# SimpleServo2.net
KiCad netlist of a schematic drawn in EAGLE
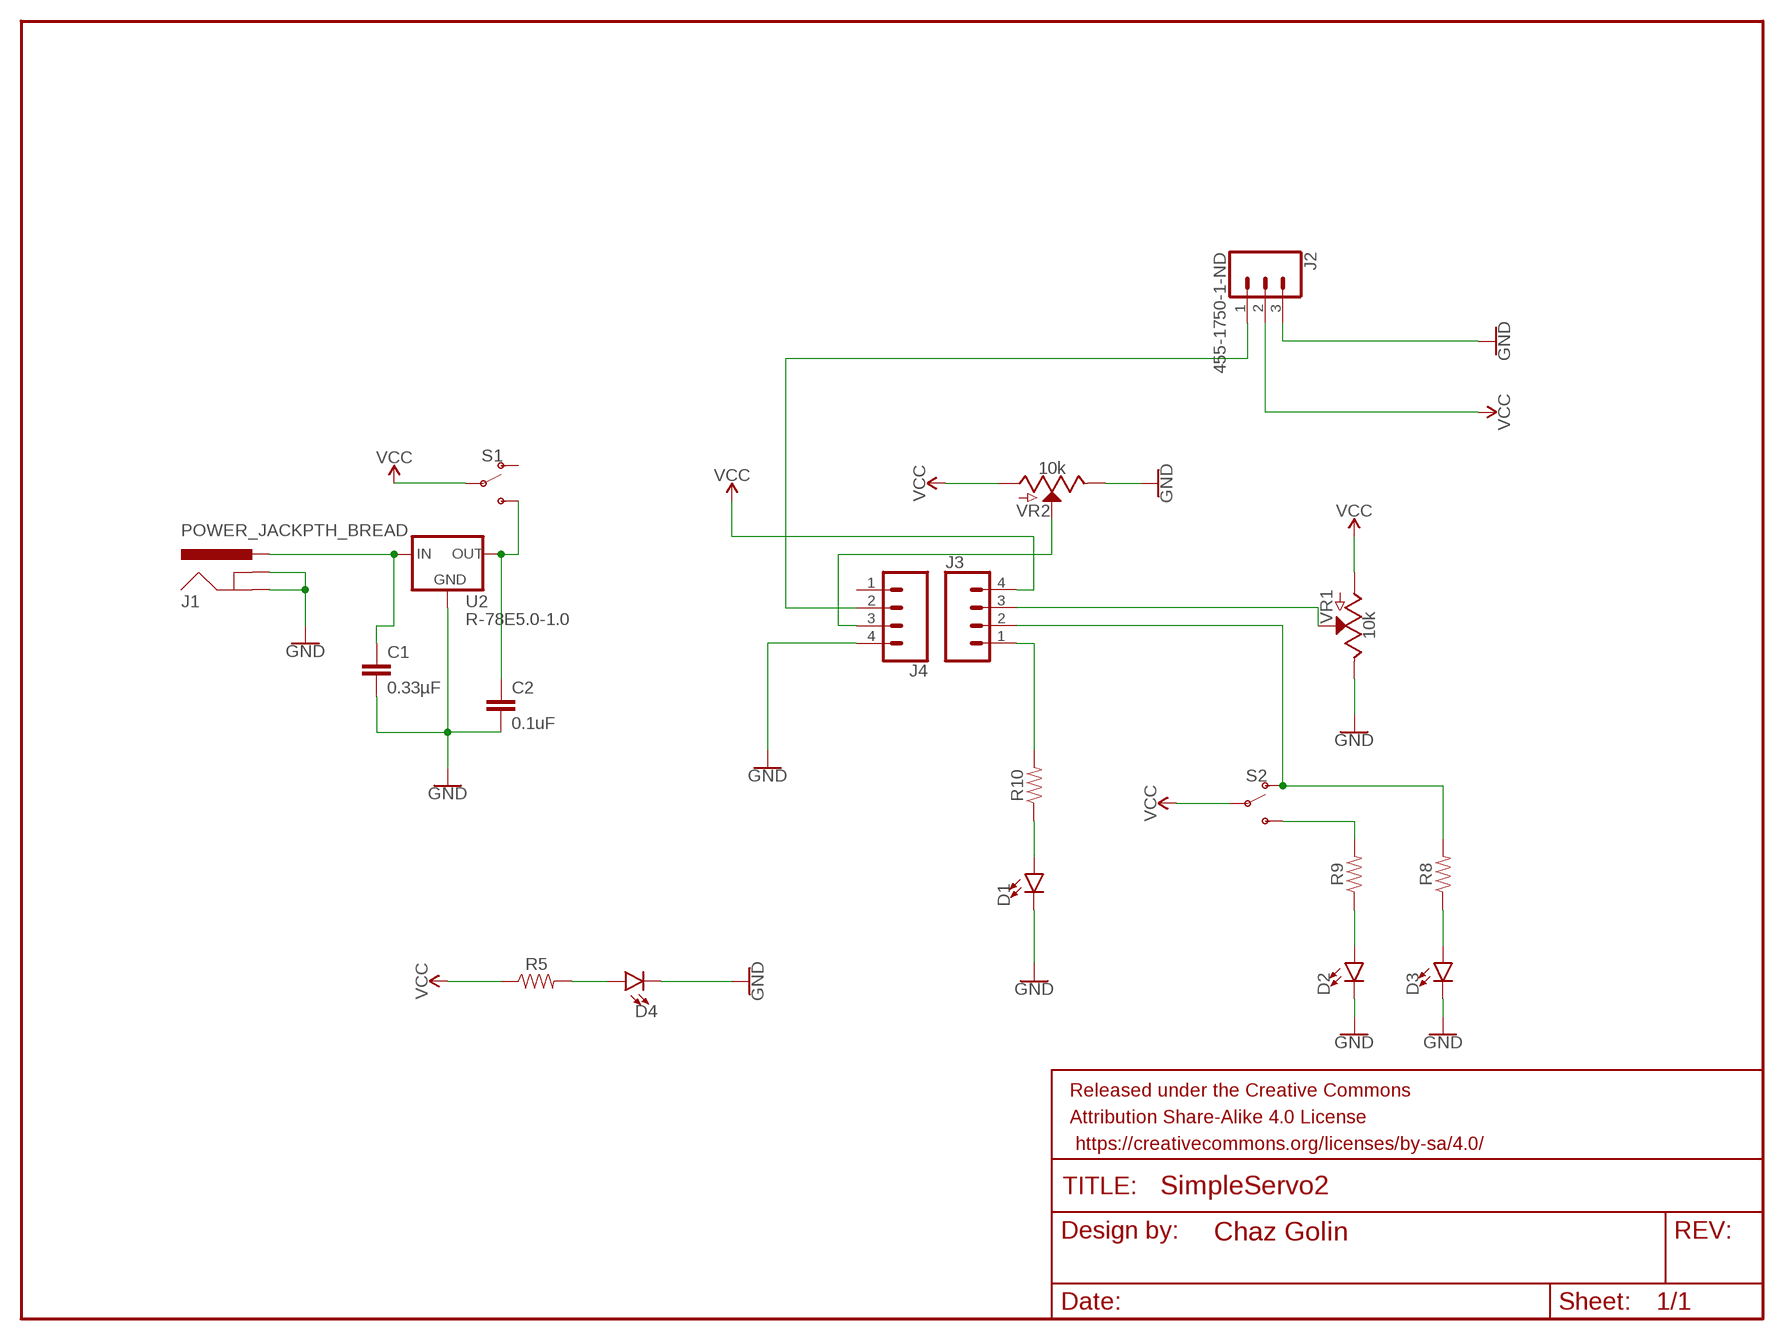
[diagram p0: schematic, sheet 1]

(export (version "E")
  (design (tool "Eeschema 10.0.6"))
  (components
    (comp (ref "C1")
      (value "0.33µF")
      (footprint "eagle-import:0805")
      (libsource (lib "eagle-import") (part "0.33UF/330NF-0805-50V-10%"))
    )
    (comp (ref "C2")
      (value "0.1uF")
      (footprint "eagle-import:0402")
      (libsource (lib "eagle-import") (part "0.1UF-0402-6.3V-10%-X7R"))
    )
    (comp (ref "D1")
      (value "LED3MM")
      (footprint "eagle-import:LED_3MM")
      (libsource (lib "eagle-import") (part "LED3MM"))
    )
    (comp (ref "D2")
      (value "LED3MM")
      (footprint "eagle-import:LED_3MM")
      (libsource (lib "eagle-import") (part "LED3MM"))
    )
    (comp (ref "D3")
      (value "LED3MM")
      (footprint "eagle-import:LED_3MM")
      (libsource (lib "eagle-import") (part "LED3MM"))
    )
    (comp (ref "D4")
      (value "LED3MM")
      (footprint "eagle-import:LED_3MM")
      (libsource (lib "eagle-import") (part "LED3MM"))
    )
    (comp (ref "FRAME1")
      (value "FRAME-LETTER")
      (footprint "eagle-import:CREATIVE_COMMONS")
      (fields (field (name "DESIGNER") "Chaz Golin"))
      (libsource (lib "eagle-import") (part "FRAME-LETTER"))
    )
    (comp (ref "J1")
      (value "POWER_JACKPTH_BREAD")
      (footprint "eagle-import:POWER_JACK_PTH_BREAD")
      (libsource (lib "eagle-import") (part "POWER_JACKPTH_BREAD"))
    )
    (comp (ref "J2")
      (value "455-1750-1-ND")
      (footprint "eagle-import:1X03")
      (libsource (lib "eagle-import") (part "CONN_03"))
    )
    (comp (ref "J3")
      (value "CONN_041X04_NO_SILK")
      (footprint "eagle-import:1X04_NO_SILK")
      (libsource (lib "eagle-import") (part "CONN_041X04_NO_SILK"))
    )
    (comp (ref "J4")
      (value "CONN_041X04_NO_SILK")
      (footprint "eagle-import:1X04_NO_SILK")
      (libsource (lib "eagle-import") (part "CONN_041X04_NO_SILK"))
    )
    (comp (ref "R5")
      (value "RESISTORAXIAL-0.3")
      (footprint "eagle-import:AXIAL-0.3")
      (libsource (lib "eagle-import") (part "RESISTORAXIAL-0.3"))
    )
    (comp (ref "R8")
      (value "RESISTORAXIAL-0.3")
      (footprint "eagle-import:AXIAL-0.3")
      (libsource (lib "eagle-import") (part "RESISTORAXIAL-0.3"))
    )
    (comp (ref "R9")
      (value "RESISTORAXIAL-0.3")
      (footprint "eagle-import:AXIAL-0.3")
      (libsource (lib "eagle-import") (part "RESISTORAXIAL-0.3"))
    )
    (comp (ref "R10")
      (value "RESISTORAXIAL-0.3")
      (footprint "eagle-import:AXIAL-0.3")
      (libsource (lib "eagle-import") (part "RESISTORAXIAL-0.3"))
    )
    (comp (ref "S1")
      (value "SWITCH-SPDT-PTH-11.6X4.0MM")
      (footprint "eagle-import:SWITCH_SPDT_PTH_11.6X4.0MM")
      (libsource (lib "eagle-import") (part "SWITCH-SPDT-PTH-11.6X4.0MM"))
    )
    (comp (ref "S2")
      (value "SWITCH-SPDT-PTH-11.6X4.0MM")
      (footprint "eagle-import:SWITCH_SPDT_PTH_11.6X4.0MM")
      (libsource (lib "eagle-import") (part "SWITCH-SPDT-PTH-11.6X4.0MM"))
    )
    (comp (ref "U2")
      (value "R-78E5.0-1.0")
      (footprint "eagle-import:DC-DC_CONVERTER_78XX")
      (libsource (lib "eagle-import") (part "R-78E5.0-1.0"))
    )
    (comp (ref "VR1")
      (value "10k")
      (footprint "eagle-import:POT-PTH-ALPS")
      (libsource (lib "eagle-import") (part "POTENTIOMETER-PTH-9MM-1/20W-20%"))
    )
    (comp (ref "VR2")
      (value "10k")
      (footprint "eagle-import:POT-PTH-ALPS")
      (libsource (lib "eagle-import") (part "POTENTIOMETER-PTH-9MM-1/20W-20%"))
    )
  )
  (nets
    (net (code "1") (name "GND") (class "Default")
      (node (ref "C1") (pin "2") (pinfunction "2_2") (pintype "passive"))
      (node (ref "C2") (pin "2") (pinfunction "2_2") (pintype "passive"))
      (node (ref "D1") (pin "K") (pinfunction "C_K") (pintype "passive"))
      (node (ref "D2") (pin "K") (pinfunction "C_K") (pintype "passive"))
      (node (ref "D3") (pin "K") (pinfunction "C_K") (pintype "passive"))
      (node (ref "D4") (pin "K") (pinfunction "C_K") (pintype "passive"))
      (node (ref "J1") (pin "GND") (pinfunction "GND_GND") (pintype "bidirectional"))
      (node (ref "J1") (pin "GNDBREAK") (pinfunction "GNDBREAK_GNDBREAK") (pintype "bidirectional"))
      (node (ref "J2") (pin "3") (pinfunction "3_3") (pintype "passive"))
      (node (ref "J4") (pin "4") (pinfunction "4_4") (pintype "passive"))
      (node (ref "U2") (pin "GND") (pinfunction "GND_GND") (pintype "input"))
      (node (ref "VR1") (pin "P$1") (pinfunction "E_P$1") (pintype "passive"))
      (node (ref "VR2") (pin "P$1") (pinfunction "E_P$1") (pintype "passive"))
    )
    (net (code "2") (name "Net-(J2-Pad1)") (class "Default")
      (node (ref "J2") (pin "1") (pinfunction "1_1") (pintype "passive"))
      (node (ref "J4") (pin "2") (pinfunction "2_2") (pintype "passive"))
    )
    (net (code "3") (name "Net-(R5-2)") (class "Default")
      (node (ref "D4") (pin "A") (pinfunction "A_A") (pintype "passive"))
      (node (ref "R5") (pin "P$2") (pinfunction "2_P$2") (pintype "passive"))
    )
    (net (code "4") (name "Net-(R8-1)") (class "Default")
      (node (ref "D3") (pin "A") (pinfunction "A_A") (pintype "passive"))
      (node (ref "R8") (pin "P$1") (pinfunction "1_P$1") (pintype "passive"))
    )
    (net (code "5") (name "Net-(R8-2)") (class "Default")
      (node (ref "J3") (pin "2") (pinfunction "2_2") (pintype "passive"))
      (node (ref "R8") (pin "P$2") (pinfunction "2_P$2") (pintype "passive"))
      (node (ref "S2") (pin "1") (pinfunction "O_1") (pintype "passive"))
    )
    (net (code "6") (name "Net-(R9-1)") (class "Default")
      (node (ref "D2") (pin "A") (pinfunction "A_A") (pintype "passive"))
      (node (ref "R9") (pin "P$1") (pinfunction "1_P$1") (pintype "passive"))
    )
    (net (code "7") (name "Net-(R9-2)") (class "Default")
      (node (ref "R9") (pin "P$2") (pinfunction "2_P$2") (pintype "passive"))
      (node (ref "S2") (pin "3") (pinfunction "S_3") (pintype "passive"))
    )
    (net (code "8") (name "Net-(R10-1)") (class "Default")
      (node (ref "D1") (pin "A") (pinfunction "A_A") (pintype "passive"))
      (node (ref "R10") (pin "P$1") (pinfunction "1_P$1") (pintype "passive"))
    )
    (net (code "9") (name "Net-(R10-2)") (class "Default")
      (node (ref "J3") (pin "1") (pinfunction "1_1") (pintype "passive"))
      (node (ref "R10") (pin "P$2") (pinfunction "2_P$2") (pintype "passive"))
    )
    (net (code "10") (name "Net-(S1-S)") (class "Default")
      (node (ref "C2") (pin "1") (pinfunction "1_1") (pintype "passive"))
      (node (ref "S1") (pin "3") (pinfunction "S_3") (pintype "passive"))
      (node (ref "U2") (pin "VOUT") (pinfunction "OUT_VOUT") (pintype "passive"))
    )
    (net (code "11") (name "Net-(U2-IN)") (class "Default")
      (node (ref "C1") (pin "1") (pinfunction "1_1") (pintype "passive"))
      (node (ref "J1") (pin "PWR") (pinfunction "PWR_PWR") (pintype "bidirectional"))
      (node (ref "U2") (pin "VIN") (pinfunction "IN_VIN") (pintype "input"))
    )
    (net (code "12") (name "Net-(VR1-S)") (class "Default")
      (node (ref "J3") (pin "3") (pinfunction "3_3") (pintype "passive"))
      (node (ref "VR1") (pin "P$2") (pinfunction "S_P$2") (pintype "passive"))
    )
    (net (code "13") (name "Net-(VR2-S)") (class "Default")
      (node (ref "J4") (pin "3") (pinfunction "3_3") (pintype "passive"))
      (node (ref "VR2") (pin "P$2") (pinfunction "S_P$2") (pintype "passive"))
    )
    (net (code "14") (name "VCC") (class "Default")
      (node (ref "J2") (pin "2") (pinfunction "2_2") (pintype "passive"))
      (node (ref "J3") (pin "4") (pinfunction "4_4") (pintype "passive"))
      (node (ref "R5") (pin "P$1") (pinfunction "1_P$1") (pintype "passive"))
      (node (ref "S1") (pin "2") (pinfunction "P_2") (pintype "passive"))
      (node (ref "S2") (pin "2") (pinfunction "P_2") (pintype "passive"))
      (node (ref "VR1") (pin "P$3") (pinfunction "A_P$3") (pintype "passive"))
      (node (ref "VR2") (pin "P$3") (pinfunction "A_P$3") (pintype "passive"))
    )
    (net (code "15") (name "unconnected-(J4-Pad1)") (class "Default")
      (node (ref "J4") (pin "1") (pinfunction "1_1") (pintype "passive"))
    )
    (net (code "16") (name "unconnected-(S1-O-Pad1)") (class "Default")
      (node (ref "S1") (pin "1") (pinfunction "O_1") (pintype "passive"))
    )
  )
)
